# LCD_board.net
KiCad netlist of a schematic drawn in EAGLE
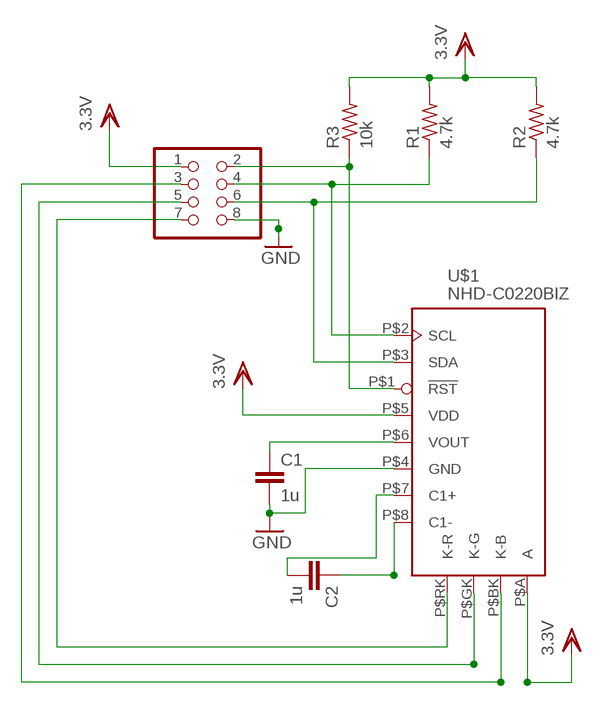
[diagram p0: schematic, sheet 1]

(export (version "E")
  (design (tool "Eeschema 10.0.6"))
  (components
    (comp (ref "C1")
      (value "1u")
      (footprint "eagle-import:C0805")
      (libsource (lib "eagle-import") (part "C"))
    )
    (comp (ref "C2")
      (value "1u")
      (footprint "eagle-import:C0805")
      (libsource (lib "eagle-import") (part "C"))
    )
    (comp (ref "DATALINES")
      (value "To MPU")
      (footprint "eagle-import:2X04")
      (libsource (lib "eagle-import") (part "PINHD-2X4"))
    )
    (comp (ref "R1")
      (value "4.7k")
      (footprint "eagle-import:M0805")
      (libsource (lib "eagle-import") (part "R-US_M0805"))
    )
    (comp (ref "R2")
      (value "4.7k")
      (footprint "eagle-import:M0805")
      (libsource (lib "eagle-import") (part "R-US_M0805"))
    )
    (comp (ref "R3")
      (value "10k")
      (footprint "eagle-import:M0805")
      (libsource (lib "eagle-import") (part "R-US_M0805"))
    )
    (comp (ref "U$1")
      (value "NHD-C0220BIZ")
      (footprint "eagle-import:NHD-C0220BIZ-LCD")
      (libsource (lib "eagle-import") (part "NHD-C0220BIZ"))
    )
  )
  (nets
    (net (code "1") (name "3.3V") (class "Default")
      (node (ref "DATALINES") (pin "1") (pinfunction "1_1") (pintype "passive"))
      (node (ref "R1") (pin "2") (pinfunction "2_2") (pintype "passive"))
      (node (ref "R2") (pin "2") (pinfunction "2_2") (pintype "passive"))
      (node (ref "R3") (pin "2") (pinfunction "2_2") (pintype "passive"))
      (node (ref "U$1") (pin "P$5") (pinfunction "VDD_P$5") (pintype "power_in"))
      (node (ref "U$1") (pin "P$A") (pinfunction "A_P$A") (pintype "bidirectional"))
    )
    (net (code "2") (name "GND") (class "Default")
      (node (ref "C1") (pin "2") (pinfunction "2_2") (pintype "passive"))
      (node (ref "DATALINES") (pin "8") (pinfunction "8_8") (pintype "passive"))
      (node (ref "U$1") (pin "P$4") (pinfunction "GND_P$4") (pintype "power_in"))
    )
    (net (code "3") (name "Net-(U$1-C1+)") (class "Default")
      (node (ref "C2") (pin "2") (pinfunction "2_2") (pintype "passive"))
      (node (ref "U$1") (pin "P$7") (pinfunction "C1+_P$7") (pintype "bidirectional"))
    )
    (net (code "4") (name "Net-(U$1-C1-)") (class "Default")
      (node (ref "C2") (pin "1") (pinfunction "1_1") (pintype "passive"))
      (node (ref "U$1") (pin "P$8") (pinfunction "C1-_P$8") (pintype "bidirectional"))
    )
    (net (code "5") (name "Net-(U$1-K-B)") (class "Default")
      (node (ref "DATALINES") (pin "3") (pinfunction "3_3") (pintype "passive"))
      (node (ref "U$1") (pin "P$BK") (pinfunction "K-B_P$BK") (pintype "bidirectional"))
    )
    (net (code "6") (name "Net-(U$1-K-G)") (class "Default")
      (node (ref "DATALINES") (pin "5") (pinfunction "5_5") (pintype "passive"))
      (node (ref "U$1") (pin "P$GK") (pinfunction "K-G_P$GK") (pintype "bidirectional"))
    )
    (net (code "7") (name "Net-(U$1-K-R)") (class "Default")
      (node (ref "DATALINES") (pin "7") (pinfunction "7_7") (pintype "passive"))
      (node (ref "U$1") (pin "P$RK") (pinfunction "K-R_P$RK") (pintype "bidirectional"))
    )
    (net (code "8") (name "Net-(U$1-SCL)") (class "Default")
      (node (ref "DATALINES") (pin "4") (pinfunction "4_4") (pintype "passive"))
      (node (ref "R1") (pin "1") (pinfunction "1_1") (pintype "passive"))
      (node (ref "U$1") (pin "P$2") (pinfunction "SCL_P$2") (pintype "bidirectional"))
    )
    (net (code "9") (name "Net-(U$1-SDA)") (class "Default")
      (node (ref "DATALINES") (pin "6") (pinfunction "6_6") (pintype "passive"))
      (node (ref "R2") (pin "1") (pinfunction "1_1") (pintype "passive"))
      (node (ref "U$1") (pin "P$3") (pinfunction "SDA_P$3") (pintype "bidirectional"))
    )
    (net (code "10") (name "Net-(U$1-VOUT)") (class "Default")
      (node (ref "C1") (pin "1") (pinfunction "1_1") (pintype "passive"))
      (node (ref "U$1") (pin "P$6") (pinfunction "VOUT_P$6") (pintype "bidirectional"))
    )
    (net (code "11") (name "Net-(U$1-~{RST})") (class "Default")
      (node (ref "DATALINES") (pin "2") (pinfunction "2_2") (pintype "passive"))
      (node (ref "R3") (pin "1") (pinfunction "1_1") (pintype "passive"))
      (node (ref "U$1") (pin "P$1") (pinfunction "~{RST}_P$1") (pintype "input"))
    )
  )
)
